# analog_Project_schematic_1.net
KiCad netlist of a schematic drawn in Altium Designer
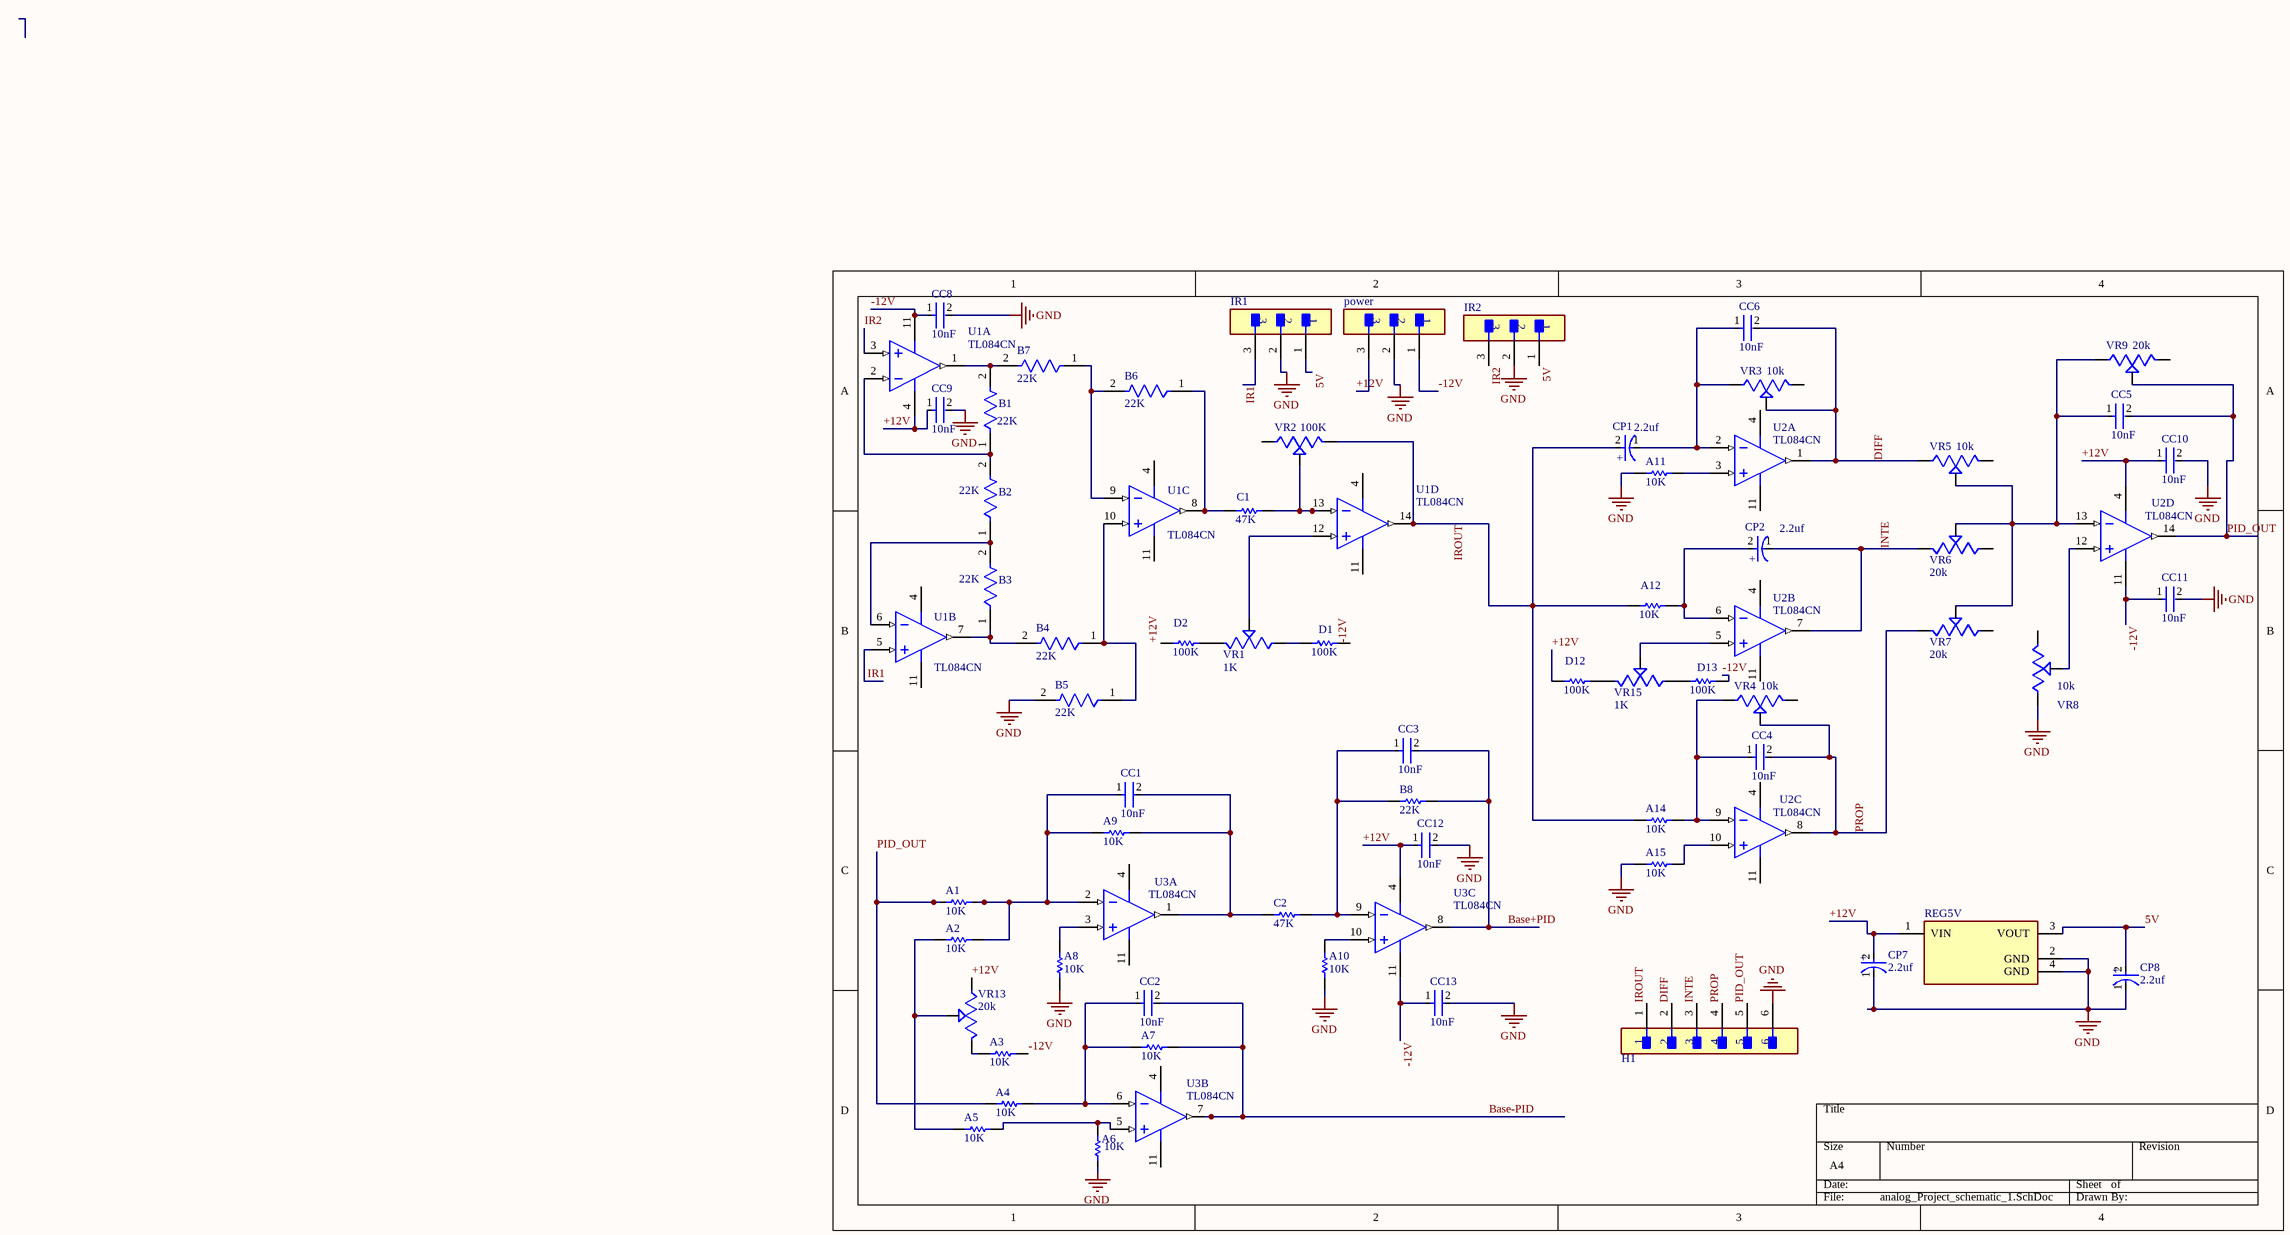
[diagram p0: analog_Project_schematic_1.SchDoc]

(export (version "E")
  (design (tool "Eeschema 10.0.6"))
  (components
    (comp (ref "A1")
      (value "10K")
      (footprint "RESC3216X70X50NL05T20")
      (fields (field (name "PART NUMBER") "ERJ-8GEYJ103V") (field (name "MANUFACTURER") "Panasonic"))
      (libsource (lib "Altium Content Vault") (part "RES"))
    )
    (comp (ref "A2")
      (value "10K")
      (footprint "RESC3216X70X50NL05T20")
      (fields (field (name "PART NUMBER") "ERJ-8GEYJ103V") (field (name "MANUFACTURER") "Panasonic"))
      (libsource (lib "Altium Content Vault") (part "RES"))
    )
    (comp (ref "A3")
      (value "10K")
      (footprint "RESC3216X70X50NL05T20")
      (fields (field (name "PART NUMBER") "ERJ-8GEYJ103V") (field (name "MANUFACTURER") "Panasonic"))
      (libsource (lib "Altium Content Vault") (part "RES"))
    )
    (comp (ref "A4")
      (value "10K")
      (footprint "RESC3216X70X50NL05T20")
      (fields (field (name "PART NUMBER") "ERJ-8GEYJ103V") (field (name "MANUFACTURER") "Panasonic"))
      (libsource (lib "Altium Content Vault") (part "RES"))
    )
    (comp (ref "A5")
      (value "10K")
      (footprint "RESC3216X70X50NL05T20")
      (fields (field (name "PART NUMBER") "ERJ-8GEYJ103V") (field (name "MANUFACTURER") "Panasonic"))
      (libsource (lib "Altium Content Vault") (part "RES"))
    )
    (comp (ref "A6")
      (value "10K")
      (footprint "RESC3216X70X50NL05T20")
      (fields (field (name "PART NUMBER") "ERJ-8GEYJ103V") (field (name "MANUFACTURER") "Panasonic"))
      (libsource (lib "Altium Content Vault") (part "RES"))
    )
    (comp (ref "A7")
      (value "10K")
      (footprint "RESC3216X70X50NL05T20")
      (fields (field (name "PART NUMBER") "ERJ-8GEYJ103V") (field (name "MANUFACTURER") "Panasonic"))
      (libsource (lib "Altium Content Vault") (part "RES"))
    )
    (comp (ref "A8")
      (value "10K")
      (footprint "RESC3216X70X50NL05T20")
      (fields (field (name "PART NUMBER") "ERJ-8GEYJ103V") (field (name "MANUFACTURER") "Panasonic"))
      (libsource (lib "Altium Content Vault") (part "RES"))
    )
    (comp (ref "A9")
      (value "10K")
      (footprint "RESC3216X70X50LL05T20")
      (fields (field (name "PART NUMBER") "ERJ-8GEYJ103V") (field (name "MANUFACTURER") "Panasonic"))
      (libsource (lib "Altium Content Vault") (part "RES"))
    )
    (comp (ref "A10")
      (value "10K")
      (footprint "RESC3216X70X50NL05T20")
      (fields (field (name "PART NUMBER") "ERJ-8GEYJ103V") (field (name "MANUFACTURER") "Panasonic"))
      (libsource (lib "Altium Content Vault") (part "RES"))
    )
    (comp (ref "A11")
      (value "10K")
      (footprint "RESC3216X70X50NL05T20")
      (fields (field (name "PART NUMBER") "ERJ-8GEYJ103V") (field (name "MANUFACTURER") "Panasonic"))
      (libsource (lib "Altium Content Vault") (part "RES"))
    )
    (comp (ref "A12")
      (value "10K")
      (footprint "RESC3216X70X50NL05T20")
      (fields (field (name "PART NUMBER") "ERJ-8GEYJ103V") (field (name "MANUFACTURER") "Panasonic"))
      (libsource (lib "Altium Content Vault") (part "RES"))
    )
    (comp (ref "A14")
      (value "10K")
      (footprint "RESC3216X70X50NL05T20")
      (fields (field (name "PART NUMBER") "ERJ-8GEYJ103V") (field (name "MANUFACTURER") "Panasonic"))
      (libsource (lib "Altium Content Vault") (part "RES"))
    )
    (comp (ref "A15")
      (value "10K")
      (footprint "RESC3216X70X50NL05T20")
      (fields (field (name "PART NUMBER") "ERJ-8GEYJ103V") (field (name "MANUFACTURER") "Panasonic"))
      (libsource (lib "Altium Content Vault") (part "RES"))
    )
    (comp (ref "B1")
      (value "22K")
      (footprint "FP-CRCW1206-e3-IPC_A")
      (description "RES Thick Film, 22kΩ, 1%, 0.25W, 100ppm/°C, 1206")
      (fields (field (name "TOLERANCE") "1%"))
      (libsource (lib "Altium Content Vault") (part "1029c3af85768c4190bb7ad29bc67b5"))
    )
    (comp (ref "B2")
      (value "22K")
      (footprint "FP-CRCW1206-e3-IPC_A")
      (description "RES Thick Film, 22kΩ, 1%, 0.25W, 100ppm/°C, 1206")
      (fields (field (name "TOLERANCE") "1%"))
      (libsource (lib "Altium Content Vault") (part "1029c3af85768c4190bb7ad29bc67b5"))
    )
    (comp (ref "B3")
      (value "22K")
      (footprint "FP-CRCW1206-e3-IPC_A")
      (description "RES Thick Film, 22kΩ, 1%, 0.25W, 100ppm/°C, 1206")
      (fields (field (name "TOLERANCE") "1%"))
      (libsource (lib "Altium Content Vault") (part "1029c3af85768c4190bb7ad29bc67b5"))
    )
    (comp (ref "B4")
      (value "22K")
      (footprint "FP-CRCW1206-e3-IPC_A")
      (description "RES Thick Film, 22kΩ, 1%, 0.25W, 100ppm/°C, 1206")
      (fields (field (name "TOLERANCE") "1%"))
      (libsource (lib "Altium Content Vault") (part "1029c3af85768c4190bb7ad29bc67b5"))
    )
    (comp (ref "B5")
      (value "22K")
      (footprint "FP-CRCW1206-e3-IPC_A")
      (description "RES Thick Film, 22kΩ, 1%, 0.25W, 100ppm/°C, 1206")
      (fields (field (name "TOLERANCE") "1%"))
      (libsource (lib "Altium Content Vault") (part "1029c3af85768c4190bb7ad29bc67b5"))
    )
    (comp (ref "B6")
      (value "22K")
      (footprint "FP-CRCW1206-e3-IPC_A")
      (description "RES Thick Film, 22kΩ, 1%, 0.25W, 100ppm/°C, 1206")
      (fields (field (name "TOLERANCE") "1%"))
      (libsource (lib "Altium Content Vault") (part "1029c3af85768c4190bb7ad29bc67b5"))
    )
    (comp (ref "B7")
      (value "22K")
      (footprint "FP-CRCW1206-e3-IPC_A")
      (description "RES Thick Film, 22kΩ, 1%, 0.25W, 100ppm/°C, 1206")
      (fields (field (name "TOLERANCE") "1%"))
      (libsource (lib "Altium Content Vault") (part "1029c3af85768c4190bb7ad29bc67b5"))
    )
    (comp (ref "B8")
      (value "22K")
      (footprint "RESC3216X60X45LL10T20")
      (fields (field (name "PART NUMBER") "CRCW120647K0FKEA") (field (name "MANUFACTURER") "Vishay Dale"))
      (libsource (lib "Altium Content Vault") (part "RES"))
    )
    (comp (ref "C1")
      (value "47K")
      (footprint "RESC3216X60X45LL10T20")
      (fields (field (name "PART NUMBER") "CRCW120647K0FKEA") (field (name "MANUFACTURER") "Vishay Dale"))
      (libsource (lib "Altium Content Vault") (part "RES"))
    )
    (comp (ref "C2")
      (value "47K")
      (footprint "RESC3216X60X45LL10T20")
      (fields (field (name "PART NUMBER") "CRCW120647K0FKEA") (field (name "MANUFACTURER") "Vishay Dale"))
      (libsource (lib "Altium Content Vault") (part "RES"))
    )
    (comp (ref "CC1")
      (value "10nF")
      (footprint "FP-C1206C-EB-MFG")
      (description "Cap Ceramic 0.01uF 100V X7R 10% SMD 1206 125°C Plastic T/R")
      (fields
        (field (name "MANUFACTURER") "KEMET")
        (field (name "MANUFACTURER PART NUMBER") "C1206C103K1RACTU")
      )
      (libsource (lib "Altium Content Vault") (part "b4654b650e69147ec39a6b967a45e02"))
    )
    (comp (ref "CC2")
      (value "10nF")
      (footprint "FP-C1206C-EB-MFG")
      (description "Cap Ceramic 0.01uF 100V X7R 10% SMD 1206 125°C Plastic T/R")
      (fields
        (field (name "MANUFACTURER") "KEMET")
        (field (name "MANUFACTURER PART NUMBER") "C1206C103K1RACTU")
      )
      (libsource (lib "Altium Content Vault") (part "b4654b650e69147ec39a6b967a45e02"))
    )
    (comp (ref "CC3")
      (value "10nF")
      (footprint "FP-C1206C-EB-MFG")
      (description "Cap Ceramic 0.01uF 100V X7R 10% SMD 1206 125°C Plastic T/R")
      (fields
        (field (name "MANUFACTURER") "KEMET")
        (field (name "MANUFACTURER PART NUMBER") "C1206C103K1RACTU")
      )
      (libsource (lib "Altium Content Vault") (part "b4654b650e69147ec39a6b967a45e02"))
    )
    (comp (ref "CC4")
      (value "10nF")
      (footprint "FP-C1206C-EB-MFG")
      (description "Cap Ceramic 0.01uF 100V X7R 10% SMD 1206 125°C Plastic T/R")
      (fields
        (field (name "MANUFACTURER") "KEMET")
        (field (name "MANUFACTURER PART NUMBER") "C1206C103K1RACTU")
      )
      (libsource (lib "Altium Content Vault") (part "b4654b650e69147ec39a6b967a45e02"))
    )
    (comp (ref "CC5")
      (value "10nF")
      (footprint "FP-C1206C-EB-MFG")
      (description "Cap Ceramic 0.01uF 100V X7R 10% SMD 1206 125°C Plastic T/R")
      (fields
        (field (name "MANUFACTURER") "KEMET")
        (field (name "MANUFACTURER PART NUMBER") "C1206C103K1RACTU")
      )
      (libsource (lib "Altium Content Vault") (part "b4654b650e69147ec39a6b967a45e02"))
    )
    (comp (ref "CC6")
      (value "10nF")
      (footprint "FP-C1206C-EB-MFG")
      (description "Cap Ceramic 0.01uF 100V X7R 10% SMD 1206 125°C Plastic T/R")
      (fields
        (field (name "MANUFACTURER") "KEMET")
        (field (name "MANUFACTURER PART NUMBER") "C1206C103K1RACTU")
      )
      (libsource (lib "Altium Content Vault") (part "b4654b650e69147ec39a6b967a45e02"))
    )
    (comp (ref "CC8")
      (value "10nF")
      (footprint "FP-C1206C-EB-MFG")
      (description "Cap Ceramic 0.01uF 100V X7R 10% SMD 1206 125°C Plastic T/R")
      (fields
        (field (name "MANUFACTURER") "KEMET")
        (field (name "MANUFACTURER PART NUMBER") "C1206C103K1RACTU")
      )
      (libsource (lib "Altium Content Vault") (part "b4654b650e69147ec39a6b967a45e02"))
    )
    (comp (ref "CC9")
      (value "10nF")
      (footprint "FP-C1206C-EB-MFG")
      (description "Cap Ceramic 0.01uF 100V X7R 10% SMD 1206 125°C Plastic T/R")
      (fields
        (field (name "MANUFACTURER") "KEMET")
        (field (name "MANUFACTURER PART NUMBER") "C1206C103K1RACTU")
      )
      (libsource (lib "Altium Content Vault") (part "b4654b650e69147ec39a6b967a45e02"))
    )
    (comp (ref "CC10")
      (value "10nF")
      (footprint "FP-C1206C-EB-MFG")
      (description "Cap Ceramic 0.01uF 100V X7R 10% SMD 1206 125°C Plastic T/R")
      (fields
        (field (name "MANUFACTURER") "KEMET")
        (field (name "MANUFACTURER PART NUMBER") "C1206C103K1RACTU")
      )
      (libsource (lib "Altium Content Vault") (part "b4654b650e69147ec39a6b967a45e02"))
    )
    (comp (ref "CC11")
      (value "10nF")
      (footprint "FP-C1206C-EB-MFG")
      (description "Cap Ceramic 0.01uF 100V X7R 10% SMD 1206 125°C Plastic T/R")
      (fields
        (field (name "MANUFACTURER") "KEMET")
        (field (name "MANUFACTURER PART NUMBER") "C1206C103K1RACTU")
      )
      (libsource (lib "Altium Content Vault") (part "b4654b650e69147ec39a6b967a45e02"))
    )
    (comp (ref "CC12")
      (value "10nF")
      (footprint "FP-C1206C-EB-MFG")
      (description "Cap Ceramic 0.01uF 100V X7R 10% SMD 1206 125°C Plastic T/R")
      (fields
        (field (name "MANUFACTURER") "KEMET")
        (field (name "MANUFACTURER PART NUMBER") "C1206C103K1RACTU")
      )
      (libsource (lib "Altium Content Vault") (part "b4654b650e69147ec39a6b967a45e02"))
    )
    (comp (ref "CC13")
      (value "10nF")
      (footprint "FP-C1206C-EB-MFG")
      (description "Cap Ceramic 0.01uF 100V X7R 10% SMD 1206 125°C Plastic T/R")
      (fields
        (field (name "MANUFACTURER") "KEMET")
        (field (name "MANUFACTURER PART NUMBER") "C1206C103K1RACTU")
      )
      (libsource (lib "Altium Content Vault") (part "b4654b650e69147ec39a6b967a45e02"))
    )
    (comp (ref "CP1")
      (value "2.2uf")
      (footprint "FP-EEU-FR1H101B-MFG")
      (description "CAP ALUM 100UF 20% 50V RADIAL")
      (fields (field (name "TOLERANCE") "20%"))
      (libsource (lib "Altium Content Vault") (part "cf48714ba7e38822c1575c7ec0b6d1f"))
    )
    (comp (ref "CP2")
      (value "2.2uf")
      (footprint "FP-EEU-FR1H101B-MFG")
      (description "CAP ALUM 100UF 20% 50V RADIAL")
      (fields (field (name "TOLERANCE") "20%"))
      (libsource (lib "Altium Content Vault") (part "cf48714ba7e38822c1575c7ec0b6d1f"))
    )
    (comp (ref "CP7")
      (value "2.2uf")
      (footprint "FP-EEU-FR1H101B-MFG")
      (description "CAP ALUM 100UF 20% 50V RADIAL")
      (fields (field (name "TOLERANCE") "20%"))
      (libsource (lib "Altium Content Vault") (part "cf48714ba7e38822c1575c7ec0b6d1f"))
    )
    (comp (ref "CP8")
      (value "2.2uf")
      (footprint "FP-EEU-FR1H101B-MFG")
      (description "CAP ALUM 100UF 20% 50V RADIAL")
      (fields (field (name "TOLERANCE") "20%"))
      (libsource (lib "Altium Content Vault") (part "cf48714ba7e38822c1575c7ec0b6d1f"))
    )
    (comp (ref "D1")
      (value "100K")
      (footprint "RESC3216X60X45NL10T20")
      (fields (field (name "PART NUMBER") "CRCW1206100KFKEA") (field (name "MANUFACTURER") "Vishay Dale"))
      (libsource (lib "Altium Content Vault") (part "RES"))
    )
    (comp (ref "D2")
      (value "100K")
      (footprint "RESC3216X60X45NL10T20")
      (fields (field (name "PART NUMBER") "CRCW1206100KFKEA") (field (name "MANUFACTURER") "Vishay Dale"))
      (libsource (lib "Altium Content Vault") (part "RES"))
    )
    (comp (ref "D12")
      (value "100K")
      (footprint "RESC3216X60X45NL10T20")
      (fields (field (name "PART NUMBER") "CRCW1206100KFKEA") (field (name "MANUFACTURER") "Vishay Dale"))
      (libsource (lib "Altium Content Vault") (part "RES"))
    )
    (comp (ref "D13")
      (value "100K")
      (footprint "RESC3216X60X45NL10T20")
      (fields (field (name "PART NUMBER") "CRCW1206100KFKEA") (field (name "MANUFACTURER") "Vishay Dale"))
      (libsource (lib "Altium Content Vault") (part "RES"))
    )
    (comp (ref "H1")
      (value "PEC06SBBN")
      (footprint "FP-PEC06SBBN-MFG")
      (description "CONN HEADER R/A 6POS 2.54MM")
      (libsource (lib "Altium Content Vault") (part "f2cb566baf1c37ab5a3b8e90bbeafd6"))
    )
    (comp (ref "IR1")
      (value "B3B-XH-A(LF)(SN)")
      (footprint "FP-B3B-XH-A_LF_SN-MFG")
      (description "CONN HEADER VERT 3POS 2.5MM")
      (libsource (lib "Altium Content Vault") (part "0d3f023dd272f625e17a2be33dea85f"))
    )
    (comp (ref "IR2")
      (value "B3B-XH-A(LF)(SN)")
      (footprint "FP-B3B-XH-A_LF_SN-MFG")
      (description "CONN HEADER VERT 3POS 2.5MM")
      (libsource (lib "Altium Content Vault") (part "0d3f023dd272f625e17a2be33dea85f"))
    )
    (comp (ref "power")
      (value "B3B-XH-A(LF)(SN)")
      (footprint "FP-B3B-XH-A_LF_SN-MFG")
      (description "CONN HEADER VERT 3POS 2.5MM")
      (libsource (lib "Altium Content Vault") (part "0d3f023dd272f625e17a2be33dea85f"))
    )
    (comp (ref "REG5V")
      (value "MC33275ST-5.0T3G")
      (footprint "FP-318E-04-IPC_A")
      (description "IC REG LINEAR 5V 300MA SOT223")
      (libsource (lib "Altium Content Vault") (part "d26761ac1ef6e5ba2d68d76a2a6affe"))
    )
    (comp (ref "U1")
      (value "TL084CN")
      (footprint "N0014A")
      (description "JFET-Input Operational Amplifier, 7 to 36 V, 0 to 70 degC, 14-pin DIP (N14), Pb-Free (RoHS)")
      (fields (field (name "MANUFACTURER") "Texas Instruments"))
      (libsource (lib "Altium Content Vault") (part "TI-TLXX4X_MC3403-X14"))
    )
    (comp (ref "U2")
      (value "TL084CN")
      (footprint "N0014A")
      (description "JFET-Input Operational Amplifier, 7 to 36 V, 0 to 70 degC, 14-pin DIP (N14), Pb-Free (RoHS)")
      (fields (field (name "MANUFACTURER") "Texas Instruments"))
      (libsource (lib "Altium Content Vault") (part "TI-TLXX4X_MC3403-X14"))
    )
    (comp (ref "U3")
      (value "TL084CN")
      (footprint "N0014A")
      (description "JFET-Input Operational Amplifier, 7 to 36 V, 0 to 70 degC, 14-pin DIP (N14), Pb-Free (RoHS)")
      (fields (field (name "MANUFACTURER") "Texas Instruments"))
      (libsource (lib "Altium Content Vault") (part "TI-TLXX4X_MC3403-X14"))
    )
    (comp (ref "VR1")
      (value "1K")
      (footprint "TRIM_3296Y-1-104")
      (fields (field (name "MP") "3296Y-1-104"))
      (libsource (lib "3296Y-1-104") (part "3296Y-1-104"))
    )
    (comp (ref "VR2")
      (value "100K")
      (footprint "TRIM_3296Y-1-104")
      (fields (field (name "MP") "3296Y-1-104"))
      (libsource (lib "3296Y-1-104") (part "3296Y-1-104"))
    )
    (comp (ref "VR3")
      (value "10k")
      (footprint "TRIM_3296Y-1-104")
      (fields (field (name "MP") "3296Y-1-104"))
      (libsource (lib "3296Y-1-104") (part "3296Y-1-104"))
    )
    (comp (ref "VR4")
      (value "10k")
      (footprint "TRIM_3296Y-1-104")
      (fields (field (name "MP") "3296Y-1-104"))
      (libsource (lib "3296Y-1-104") (part "3296Y-1-104"))
    )
    (comp (ref "VR5")
      (value "10k")
      (footprint "TRIM_3296Y-1-104")
      (fields (field (name "MP") "3296Y-1-104"))
      (libsource (lib "3296Y-1-104") (part "3296Y-1-104"))
    )
    (comp (ref "VR6")
      (value "20k")
      (footprint "TRIM_3296Y-1-104")
      (fields (field (name "MP") "3296Y-1-104"))
      (libsource (lib "3296Y-1-104") (part "3296Y-1-104"))
    )
    (comp (ref "VR7")
      (value "20k")
      (footprint "TRIM_3296Y-1-104")
      (fields (field (name "MP") "3296Y-1-104"))
      (libsource (lib "3296Y-1-104") (part "3296Y-1-104"))
    )
    (comp (ref "VR8")
      (value "10k")
      (footprint "TRIM_3296Y-1-104")
      (fields (field (name "MP") "3296Y-1-104"))
      (libsource (lib "3296Y-1-104") (part "3296Y-1-104"))
    )
    (comp (ref "VR9")
      (value "20k")
      (footprint "TRIM_3296Y-1-104")
      (fields (field (name "MP") "3296Y-1-104"))
      (libsource (lib "3296Y-1-104") (part "3296Y-1-104"))
    )
    (comp (ref "VR13")
      (value "20k")
      (footprint "TRIM_3296Y-1-104")
      (fields (field (name "MP") "3296Y-1-104"))
      (libsource (lib "3296Y-1-104") (part "3296Y-1-104"))
    )
    (comp (ref "VR15")
      (value "1K")
      (footprint "TRIM_3296Y-1-104")
      (fields (field (name "MP") "3296Y-1-104"))
      (libsource (lib "3296Y-1-104") (part "3296Y-1-104"))
    )
  )
  (nets
    (net (code "1") (name "/+12V") (class "Default")
      (node (ref "CC10") (pin "1") (pinfunction "1_1") (pintype "passive"))
      (node (ref "CC12") (pin "1") (pinfunction "1_1") (pintype "passive"))
      (node (ref "CC9") (pin "1") (pinfunction "1_1") (pintype "passive"))
      (node (ref "CP7") (pin "2") (pinfunction "A_2") (pintype "passive"))
      (node (ref "D12") (pin "1") (pinfunction "1_1") (pintype "passive"))
      (node (ref "D2") (pin "1") (pinfunction "1_1") (pintype "passive"))
      (node (ref "REG5V") (pin "1") (pinfunction "VIN_1") (pintype "power_in"))
      (node (ref "U1") (pin "4") (pinfunction "VCC+_4") (pintype "power_in"))
      (node (ref "U2") (pin "4") (pinfunction "VCC+_4") (pintype "power_in"))
      (node (ref "U3") (pin "4") (pinfunction "VCC+_4") (pintype "power_in"))
      (node (ref "VR13") (pin "1") (pinfunction "CCW_1") (pintype "passive"))
      (node (ref "power") (pin "3") (pinfunction "3_3") (pintype "passive"))
    )
    (net (code "2") (name "/-12V") (class "Default")
      (node (ref "A3") (pin "2") (pinfunction "2_2") (pintype "passive"))
      (node (ref "CC11") (pin "1") (pinfunction "1_1") (pintype "passive"))
      (node (ref "CC13") (pin "1") (pinfunction "1_1") (pintype "passive"))
      (node (ref "CC8") (pin "1") (pinfunction "1_1") (pintype "passive"))
      (node (ref "D1") (pin "2") (pinfunction "2_2") (pintype "passive"))
      (node (ref "D13") (pin "2") (pinfunction "2_2") (pintype "passive"))
      (node (ref "U1") (pin "11") (pinfunction "VCC-_11") (pintype "power_in"))
      (node (ref "U2") (pin "11") (pinfunction "VCC-_11") (pintype "power_in"))
      (node (ref "U3") (pin "11") (pinfunction "VCC-_11") (pintype "power_in"))
      (node (ref "power") (pin "1") (pinfunction "1_1") (pintype "passive"))
    )
    (net (code "3") (name "/5V") (class "Default")
      (node (ref "CP8") (pin "2") (pinfunction "A_2") (pintype "passive"))
      (node (ref "IR1") (pin "1") (pinfunction "1_1") (pintype "passive"))
      (node (ref "IR2") (pin "1") (pinfunction "1_1") (pintype "passive"))
      (node (ref "REG5V") (pin "3") (pinfunction "VOUT_3") (pintype "power_in"))
    )
    (net (code "4") (name "/Base+PID") (class "Default")
      (node (ref "B8") (pin "2") (pinfunction "2_2") (pintype "passive"))
      (node (ref "CC3") (pin "2") (pinfunction "2_2") (pintype "passive"))
      (node (ref "U3") (pin "8") (pinfunction "OUT3_8") (pintype "output"))
    )
    (net (code "5") (name "/Base-PID") (class "Default")
      (node (ref "A7") (pin "2") (pinfunction "2_2") (pintype "passive"))
      (node (ref "CC2") (pin "2") (pinfunction "2_2") (pintype "passive"))
      (node (ref "U3") (pin "7") (pinfunction "OUT2_7") (pintype "output"))
    )
    (net (code "6") (name "/DIFF") (class "Default")
      (node (ref "CC6") (pin "2") (pinfunction "2_2") (pintype "passive"))
      (node (ref "H1") (pin "2") (pinfunction "2_2") (pintype "passive"))
      (node (ref "U2") (pin "1") (pinfunction "OUT1_1") (pintype "output"))
      (node (ref "VR3") (pin "2") (pinfunction "WIPER_2") (pintype "passive"))
      (node (ref "VR5") (pin "3") (pinfunction "CW_3") (pintype "passive"))
    )
    (net (code "7") (name "/INTE") (class "Default")
      (node (ref "CP2") (pin "1") (pinfunction "C_1") (pintype "passive"))
      (node (ref "H1") (pin "3") (pinfunction "3_3") (pintype "passive"))
      (node (ref "U2") (pin "7") (pinfunction "OUT2_7") (pintype "output"))
      (node (ref "VR6") (pin "3") (pinfunction "CW_3") (pintype "passive"))
    )
    (net (code "8") (name "/IR1") (class "Default")
      (node (ref "IR1") (pin "3") (pinfunction "3_3") (pintype "passive"))
      (node (ref "U1") (pin "5") (pinfunction "IN2+_5") (pintype "input"))
    )
    (net (code "9") (name "/IR2") (class "Default")
      (node (ref "IR2") (pin "3") (pinfunction "3_3") (pintype "passive"))
      (node (ref "U1") (pin "3") (pinfunction "IN1+_3") (pintype "input"))
    )
    (net (code "10") (name "/IROUT") (class "Default")
      (node (ref "A12") (pin "1") (pinfunction "1_1") (pintype "passive"))
      (node (ref "A14") (pin "1") (pinfunction "1_1") (pintype "passive"))
      (node (ref "CP1") (pin "2") (pinfunction "A_2") (pintype "passive"))
      (node (ref "H1") (pin "1") (pinfunction "1_1") (pintype "passive"))
      (node (ref "U1") (pin "14") (pinfunction "OUT4_14") (pintype "output"))
      (node (ref "VR2") (pin "1") (pinfunction "CCW_1") (pintype "passive"))
    )
    (net (code "11") (name "/PID_OUT") (class "Default")
      (node (ref "A1") (pin "1") (pinfunction "1_1") (pintype "passive"))
      (node (ref "A4") (pin "1") (pinfunction "1_1") (pintype "passive"))
      (node (ref "CC5") (pin "2") (pinfunction "2_2") (pintype "passive"))
      (node (ref "H1") (pin "5") (pinfunction "5_5") (pintype "passive"))
      (node (ref "U2") (pin "14") (pinfunction "OUT4_14") (pintype "output"))
      (node (ref "VR9") (pin "2") (pinfunction "WIPER_2") (pintype "passive"))
    )
    (net (code "12") (name "/PROP") (class "Default")
      (node (ref "CC4") (pin "2") (pinfunction "2_2") (pintype "passive"))
      (node (ref "H1") (pin "4") (pinfunction "4_4") (pintype "passive"))
      (node (ref "U2") (pin "8") (pinfunction "OUT3_8") (pintype "output"))
      (node (ref "VR4") (pin "2") (pinfunction "WIPER_2") (pintype "passive"))
      (node (ref "VR7") (pin "3") (pinfunction "CW_3") (pintype "passive"))
    )
    (net (code "13") (name "GND") (class "Default")
      (node (ref "A10") (pin "1") (pinfunction "1_1") (pintype "passive"))
      (node (ref "A11") (pin "1") (pinfunction "1_1") (pintype "passive"))
      (node (ref "A15") (pin "1") (pinfunction "1_1") (pintype "passive"))
      (node (ref "A6") (pin "1") (pinfunction "1_1") (pintype "passive"))
      (node (ref "A8") (pin "1") (pinfunction "1_1") (pintype "passive"))
      (node (ref "B5") (pin "2") (pinfunction "2_2") (pintype "passive"))
      (node (ref "CC10") (pin "2") (pinfunction "2_2") (pintype "passive"))
      (node (ref "CC11") (pin "2") (pinfunction "2_2") (pintype "passive"))
      (node (ref "CC12") (pin "2") (pinfunction "2_2") (pintype "passive"))
      (node (ref "CC13") (pin "2") (pinfunction "2_2") (pintype "passive"))
      (node (ref "CC8") (pin "2") (pinfunction "2_2") (pintype "passive"))
      (node (ref "CC9") (pin "2") (pinfunction "2_2") (pintype "passive"))
      (node (ref "CP7") (pin "1") (pinfunction "C_1") (pintype "passive"))
      (node (ref "CP8") (pin "1") (pinfunction "C_1") (pintype "passive"))
      (node (ref "H1") (pin "6") (pinfunction "6_6") (pintype "passive"))
      (node (ref "IR1") (pin "2") (pinfunction "2_2") (pintype "passive"))
      (node (ref "IR2") (pin "2") (pinfunction "2_2") (pintype "passive"))
      (node (ref "REG5V") (pin "2") (pinfunction "GND_2") (pintype "power_in"))
      (node (ref "REG5V") (pin "4") (pinfunction "GND_4") (pintype "power_in"))
      (node (ref "VR8") (pin "3") (pinfunction "CW_3") (pintype "passive"))
      (node (ref "power") (pin "2") (pinfunction "2_2") (pintype "passive"))
    )
    (net (code "14") (name "Net-(CP1-C)") (class "Default")
      (node (ref "CC6") (pin "1") (pinfunction "1_1") (pintype "passive"))
      (node (ref "CP1") (pin "1") (pinfunction "C_1") (pintype "passive"))
      (node (ref "U2") (pin "2") (pinfunction "IN1-_2") (pintype "input"))
      (node (ref "VR3") (pin "3") (pinfunction "CW_3") (pintype "passive"))
    )
    (net (code "15") (name "Net-(CP2-A)") (class "Default")
      (node (ref "A12") (pin "2") (pinfunction "2_2") (pintype "passive"))
      (node (ref "CP2") (pin "2") (pinfunction "A_2") (pintype "passive"))
      (node (ref "U2") (pin "6") (pinfunction "IN2-_6") (pintype "input"))
    )
    (net (code "16") (name "Net-(U1A-IN1-)") (class "Default")
      (node (ref "B1") (pin "1") (pinfunction "1_1") (pintype "passive"))
      (node (ref "B2") (pin "2") (pinfunction "2_2") (pintype "passive"))
      (node (ref "U1") (pin "2") (pinfunction "IN1-_2") (pintype "input"))
    )
    (net (code "17") (name "Net-(U1A-OUT1)") (class "Default")
      (node (ref "B1") (pin "2") (pinfunction "2_2") (pintype "passive"))
      (node (ref "B7") (pin "2") (pinfunction "2_2") (pintype "passive"))
      (node (ref "U1") (pin "1") (pinfunction "OUT1_1") (pintype "output"))
    )
    (net (code "18") (name "Net-(U1B-IN2-)") (class "Default")
      (node (ref "B2") (pin "1") (pinfunction "1_1") (pintype "passive"))
      (node (ref "B3") (pin "2") (pinfunction "2_2") (pintype "passive"))
      (node (ref "U1") (pin "6") (pinfunction "IN2-_6") (pintype "input"))
    )
    (net (code "19") (name "Net-(U1B-OUT2)") (class "Default")
      (node (ref "B3") (pin "1") (pinfunction "1_1") (pintype "passive"))
      (node (ref "B4") (pin "2") (pinfunction "2_2") (pintype "passive"))
      (node (ref "U1") (pin "7") (pinfunction "OUT2_7") (pintype "output"))
    )
    (net (code "20") (name "Net-(U1C-IN3+)") (class "Default")
      (node (ref "B4") (pin "1") (pinfunction "1_1") (pintype "passive"))
      (node (ref "B5") (pin "1") (pinfunction "1_1") (pintype "passive"))
      (node (ref "U1") (pin "10") (pinfunction "IN3+_10") (pintype "input"))
    )
    (net (code "21") (name "Net-(U1C-IN3-)") (class "Default")
      (node (ref "B6") (pin "2") (pinfunction "2_2") (pintype "passive"))
      (node (ref "B7") (pin "1") (pinfunction "1_1") (pintype "passive"))
      (node (ref "U1") (pin "9") (pinfunction "IN3-_9") (pintype "input"))
    )
    (net (code "22") (name "Net-(U1C-OUT3)") (class "Default")
      (node (ref "B6") (pin "1") (pinfunction "1_1") (pintype "passive"))
      (node (ref "C1") (pin "1") (pinfunction "1_1") (pintype "passive"))
      (node (ref "U1") (pin "8") (pinfunction "OUT3_8") (pintype "output"))
    )
    (net (code "23") (name "Net-(U1D-IN4+)") (class "Default")
      (node (ref "U1") (pin "12") (pinfunction "IN4+_12") (pintype "input"))
      (node (ref "VR1") (pin "2") (pinfunction "WIPER_2") (pintype "passive"))
    )
    (net (code "24") (name "Net-(U1D-IN4-)") (class "Default")
      (node (ref "C1") (pin "2") (pinfunction "2_2") (pintype "passive"))
      (node (ref "U1") (pin "13") (pinfunction "IN4-_13") (pintype "input"))
      (node (ref "VR2") (pin "2") (pinfunction "WIPER_2") (pintype "passive"))
    )
    (net (code "25") (name "Net-(U2A-IN1+)") (class "Default")
      (node (ref "A11") (pin "2") (pinfunction "2_2") (pintype "passive"))
      (node (ref "U2") (pin "3") (pinfunction "IN1+_3") (pintype "input"))
    )
    (net (code "26") (name "Net-(U2B-IN2+)") (class "Default")
      (node (ref "U2") (pin "5") (pinfunction "IN2+_5") (pintype "input"))
      (node (ref "VR15") (pin "2") (pinfunction "WIPER_2") (pintype "passive"))
    )
    (net (code "27") (name "Net-(U2C-IN3+)") (class "Default")
      (node (ref "A15") (pin "2") (pinfunction "2_2") (pintype "passive"))
      (node (ref "U2") (pin "10") (pinfunction "IN3+_10") (pintype "input"))
    )
    (net (code "28") (name "Net-(U2C-IN3-)") (class "Default")
      (node (ref "A14") (pin "2") (pinfunction "2_2") (pintype "passive"))
      (node (ref "CC4") (pin "1") (pinfunction "1_1") (pintype "passive"))
      (node (ref "U2") (pin "9") (pinfunction "IN3-_9") (pintype "input"))
      (node (ref "VR4") (pin "3") (pinfunction "CW_3") (pintype "passive"))
    )
    (net (code "29") (name "Net-(U2D-IN4+)") (class "Default")
      (node (ref "U2") (pin "12") (pinfunction "IN4+_12") (pintype "input"))
      (node (ref "VR8") (pin "2") (pinfunction "WIPER_2") (pintype "passive"))
    )
    (net (code "30") (name "Net-(U2D-IN4-)") (class "Default")
      (node (ref "CC5") (pin "1") (pinfunction "1_1") (pintype "passive"))
      (node (ref "U2") (pin "13") (pinfunction "IN4-_13") (pintype "input"))
      (node (ref "VR5") (pin "2") (pinfunction "WIPER_2") (pintype "passive"))
      (node (ref "VR6") (pin "2") (pinfunction "WIPER_2") (pintype "passive"))
      (node (ref "VR7") (pin "2") (pinfunction "WIPER_2") (pintype "passive"))
      (node (ref "VR9") (pin "3") (pinfunction "CW_3") (pintype "passive"))
    )
    (net (code "31") (name "Net-(U3A-IN1+)") (class "Default")
      (node (ref "A8") (pin "2") (pinfunction "2_2") (pintype "passive"))
      (node (ref "U3") (pin "3") (pinfunction "IN1+_3") (pintype "input"))
    )
    (net (code "32") (name "Net-(U3A-IN1-)") (class "Default")
      (node (ref "A1") (pin "2") (pinfunction "2_2") (pintype "passive"))
      (node (ref "A2") (pin "2") (pinfunction "2_2") (pintype "passive"))
      (node (ref "A9") (pin "1") (pinfunction "1_1") (pintype "passive"))
      (node (ref "CC1") (pin "1") (pinfunction "1_1") (pintype "passive"))
      (node (ref "U3") (pin "2") (pinfunction "IN1-_2") (pintype "input"))
    )
    (net (code "33") (name "Net-(U3A-OUT1)") (class "Default")
      (node (ref "A9") (pin "2") (pinfunction "2_2") (pintype "passive"))
      (node (ref "C2") (pin "1") (pinfunction "1_1") (pintype "passive"))
      (node (ref "CC1") (pin "2") (pinfunction "2_2") (pintype "passive"))
      (node (ref "U3") (pin "1") (pinfunction "OUT1_1") (pintype "output"))
    )
    (net (code "34") (name "Net-(U3B-IN2+)") (class "Default")
      (node (ref "A5") (pin "2") (pinfunction "2_2") (pintype "passive"))
      (node (ref "A6") (pin "2") (pinfunction "2_2") (pintype "passive"))
      (node (ref "U3") (pin "5") (pinfunction "IN2+_5") (pintype "input"))
    )
    (net (code "35") (name "Net-(U3B-IN2-)") (class "Default")
      (node (ref "A4") (pin "2") (pinfunction "2_2") (pintype "passive"))
      (node (ref "A7") (pin "1") (pinfunction "1_1") (pintype "passive"))
      (node (ref "CC2") (pin "1") (pinfunction "1_1") (pintype "passive"))
      (node (ref "U3") (pin "6") (pinfunction "IN2-_6") (pintype "input"))
    )
    (net (code "36") (name "Net-(U3C-IN3+)") (class "Default")
      (node (ref "A10") (pin "2") (pinfunction "2_2") (pintype "passive"))
      (node (ref "U3") (pin "10") (pinfunction "IN3+_10") (pintype "input"))
    )
    (net (code "37") (name "Net-(U3C-IN3-)") (class "Default")
      (node (ref "B8") (pin "1") (pinfunction "1_1") (pintype "passive"))
      (node (ref "C2") (pin "2") (pinfunction "2_2") (pintype "passive"))
      (node (ref "CC3") (pin "1") (pinfunction "1_1") (pintype "passive"))
      (node (ref "U3") (pin "9") (pinfunction "IN3-_9") (pintype "input"))
    )
    (net (code "38") (name "Net-(VR1-CCW)") (class "Default")
      (node (ref "D2") (pin "2") (pinfunction "2_2") (pintype "passive"))
      (node (ref "VR1") (pin "1") (pinfunction "CCW_1") (pintype "passive"))
    )
    (net (code "39") (name "Net-(VR1-CW)") (class "Default")
      (node (ref "D1") (pin "1") (pinfunction "1_1") (pintype "passive"))
      (node (ref "VR1") (pin "3") (pinfunction "CW_3") (pintype "passive"))
    )
    (net (code "40") (name "Net-(VR13-CW)") (class "Default")
      (node (ref "A3") (pin "1") (pinfunction "1_1") (pintype "passive"))
      (node (ref "VR13") (pin "3") (pinfunction "CW_3") (pintype "passive"))
    )
    (net (code "41") (name "Net-(VR13-WIPER)") (class "Default")
      (node (ref "A2") (pin "1") (pinfunction "1_1") (pintype "passive"))
      (node (ref "A5") (pin "1") (pinfunction "1_1") (pintype "passive"))
      (node (ref "VR13") (pin "2") (pinfunction "WIPER_2") (pintype "passive"))
    )
    (net (code "42") (name "Net-(VR15-CCW)") (class "Default")
      (node (ref "D12") (pin "2") (pinfunction "2_2") (pintype "passive"))
      (node (ref "VR15") (pin "1") (pinfunction "CCW_1") (pintype "passive"))
    )
    (net (code "43") (name "Net-(VR15-CW)") (class "Default")
      (node (ref "D13") (pin "1") (pinfunction "1_1") (pintype "passive"))
      (node (ref "VR15") (pin "3") (pinfunction "CW_3") (pintype "passive"))
    )
    (net (code "44") (name "unconnected-(U1B-VCC+-Pad4)") (class "Default")
      (node (ref "U1") (pin "4") (pinfunction "VCC+_4") (pintype "power_in"))
    )
    (net (code "45") (name "unconnected-(U1B-VCC--Pad11)") (class "Default")
      (node (ref "U1") (pin "11") (pinfunction "VCC-_11") (pintype "power_in"))
    )
    (net (code "46") (name "unconnected-(U1C-VCC+-Pad4)") (class "Default")
      (node (ref "U1") (pin "4") (pinfunction "VCC+_4") (pintype "power_in"))
    )
    (net (code "47") (name "unconnected-(U1C-VCC--Pad11)") (class "Default")
      (node (ref "U1") (pin "11") (pinfunction "VCC-_11") (pintype "power_in"))
    )
    (net (code "48") (name "unconnected-(U1D-VCC+-Pad4)") (class "Default")
      (node (ref "U1") (pin "4") (pinfunction "VCC+_4") (pintype "power_in"))
    )
    (net (code "49") (name "unconnected-(U1D-VCC--Pad11)") (class "Default")
      (node (ref "U1") (pin "11") (pinfunction "VCC-_11") (pintype "power_in"))
    )
    (net (code "50") (name "unconnected-(U2A-VCC+-Pad4)") (class "Default")
      (node (ref "U2") (pin "4") (pinfunction "VCC+_4") (pintype "power_in"))
    )
    (net (code "51") (name "unconnected-(U2A-VCC--Pad11)") (class "Default")
      (node (ref "U2") (pin "11") (pinfunction "VCC-_11") (pintype "power_in"))
    )
    (net (code "52") (name "unconnected-(U2B-VCC+-Pad4)") (class "Default")
      (node (ref "U2") (pin "4") (pinfunction "VCC+_4") (pintype "power_in"))
    )
    (net (code "53") (name "unconnected-(U2B-VCC--Pad11)") (class "Default")
      (node (ref "U2") (pin "11") (pinfunction "VCC-_11") (pintype "power_in"))
    )
    (net (code "54") (name "unconnected-(U2C-VCC+-Pad4)") (class "Default")
      (node (ref "U2") (pin "4") (pinfunction "VCC+_4") (pintype "power_in"))
    )
    (net (code "55") (name "unconnected-(U2C-VCC--Pad11)") (class "Default")
      (node (ref "U2") (pin "11") (pinfunction "VCC-_11") (pintype "power_in"))
    )
    (net (code "56") (name "unconnected-(U3A-VCC+-Pad4)") (class "Default")
      (node (ref "U3") (pin "4") (pinfunction "VCC+_4") (pintype "power_in"))
    )
    (net (code "57") (name "unconnected-(U3A-VCC--Pad11)") (class "Default")
      (node (ref "U3") (pin "11") (pinfunction "VCC-_11") (pintype "power_in"))
    )
    (net (code "58") (name "unconnected-(U3B-VCC+-Pad4)") (class "Default")
      (node (ref "U3") (pin "4") (pinfunction "VCC+_4") (pintype "power_in"))
    )
    (net (code "59") (name "unconnected-(U3B-VCC--Pad11)") (class "Default")
      (node (ref "U3") (pin "11") (pinfunction "VCC-_11") (pintype "power_in"))
    )
    (net (code "60") (name "unconnected-(VR2-CW-Pad3)") (class "Default")
      (node (ref "VR2") (pin "3") (pinfunction "CW_3") (pintype "passive"))
    )
    (net (code "61") (name "unconnected-(VR3-CCW-Pad1)") (class "Default")
      (node (ref "VR3") (pin "1") (pinfunction "CCW_1") (pintype "passive"))
    )
    (net (code "62") (name "unconnected-(VR4-CCW-Pad1)") (class "Default")
      (node (ref "VR4") (pin "1") (pinfunction "CCW_1") (pintype "passive"))
    )
    (net (code "63") (name "unconnected-(VR5-CCW-Pad1)") (class "Default")
      (node (ref "VR5") (pin "1") (pinfunction "CCW_1") (pintype "passive"))
    )
    (net (code "64") (name "unconnected-(VR6-CCW-Pad1)") (class "Default")
      (node (ref "VR6") (pin "1") (pinfunction "CCW_1") (pintype "passive"))
    )
    (net (code "65") (name "unconnected-(VR7-CCW-Pad1)") (class "Default")
      (node (ref "VR7") (pin "1") (pinfunction "CCW_1") (pintype "passive"))
    )
    (net (code "66") (name "unconnected-(VR8-CCW-Pad1)") (class "Default")
      (node (ref "VR8") (pin "1") (pinfunction "CCW_1") (pintype "passive"))
    )
    (net (code "67") (name "unconnected-(VR9-CCW-Pad1)") (class "Default")
      (node (ref "VR9") (pin "1") (pinfunction "CCW_1") (pintype "passive"))
    )
  )
)
